# AUDIO.net
KiCad netlist of a schematic drawn in Altium Designer
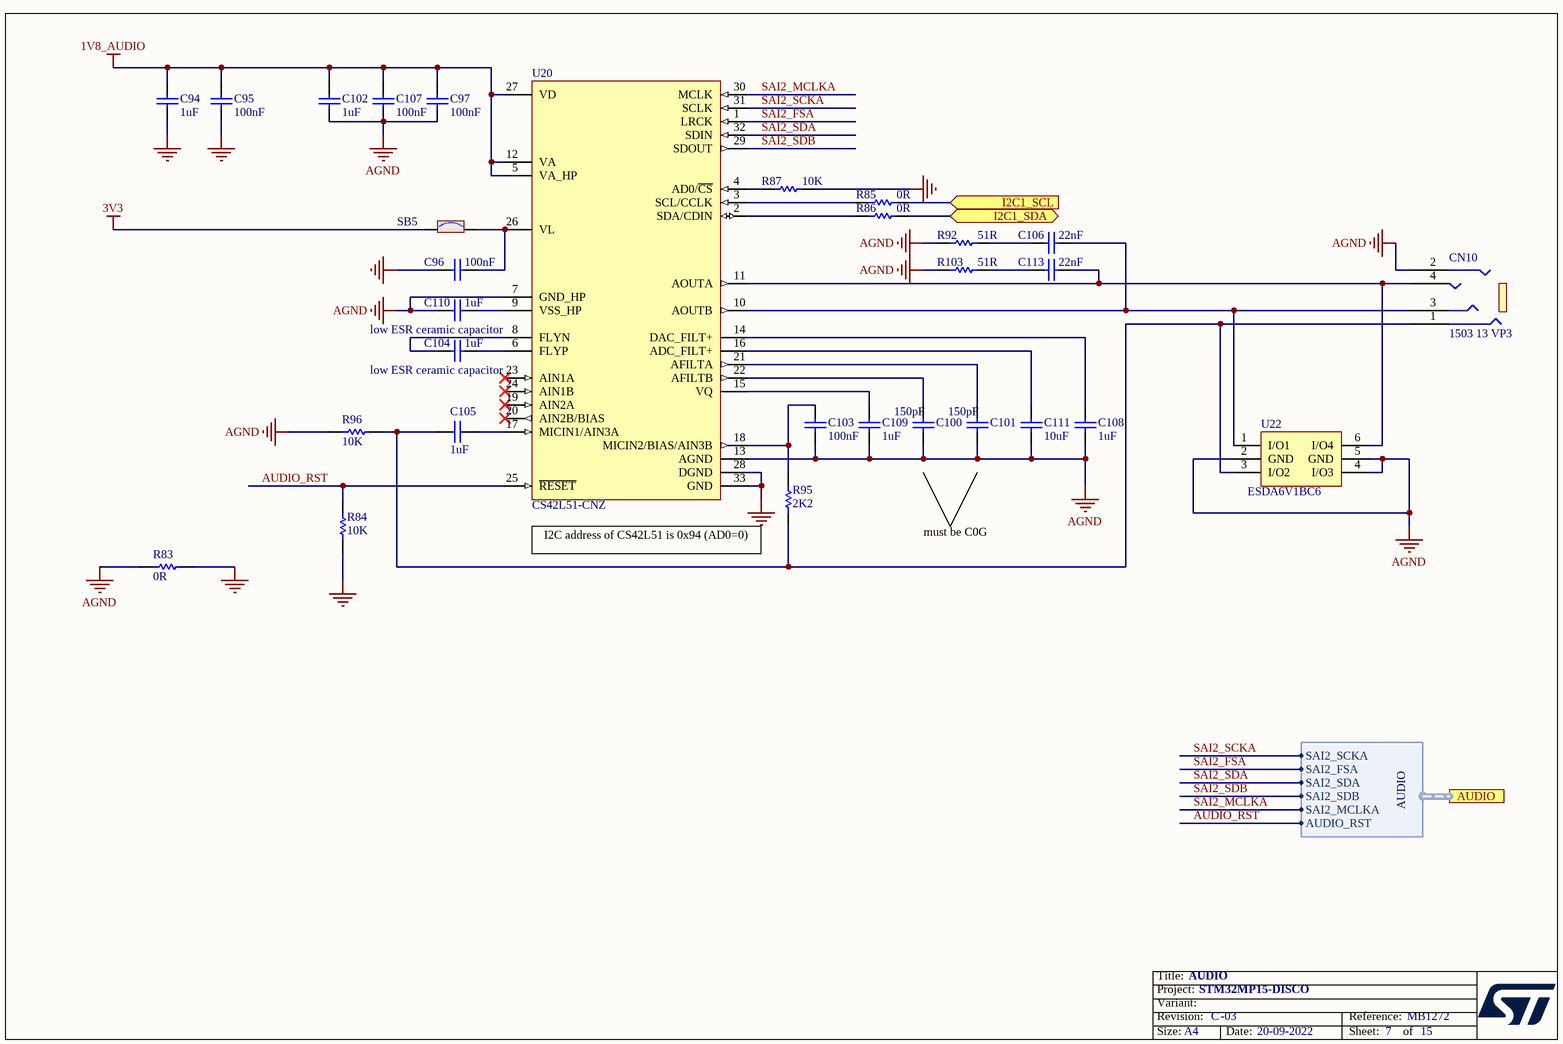
[diagram p0: AUDIO.SchDoc]

(export (version "E")
  (design (tool "Eeschema 10.0.6"))
  (components
    (comp (ref "C94")
      (value "1uF")
      (footprint "C0402")
      (description "Capacitor,1uF,6V3,X5R,10%,0402")
      (fields
        (field (name "INTERNAL_PART_NUMBER") "MCD-00095")
        (field (name "MANUFACTURER_PART_NUMBER") "GRM155R61E105KA12")
        (field (name "PROVIDED_BY") "SUBCO")
      )
      (libsource (lib "MCD_PARTS_database") (part "Capacitor"))
    )
    (comp (ref "C95")
      (value "100nF")
      (footprint "C0402")
      (description "Capacitor,100nF,16V,X7R,10%,0402")
      (fields
        (field (name "INTERNAL_PART_NUMBER") "MCD-00006")
        (field (name "MANUFACTURER_PART_NUMBER") "CC0402KRX7R7BB104")
        (field (name "PROVIDED_BY") "SUBCO")
      )
      (libsource (lib "MCD_PARTS_database") (part "Capacitor"))
    )
    (comp (ref "C96")
      (value "100nF")
      (footprint "C0402")
      (description "Capacitor,100nF,16V,X7R,10%,0402")
      (fields
        (field (name "INTERNAL_PART_NUMBER") "MCD-00006")
        (field (name "MANUFACTURER_PART_NUMBER") "CC0402KRX7R7BB104")
        (field (name "PROVIDED_BY") "SUBCO")
      )
      (libsource (lib "MCD_PARTS_database") (part "Capacitor"))
    )
    (comp (ref "C97")
      (value "100nF")
      (footprint "C0402")
      (description "Capacitor,100nF,16V,X7R,10%,0402")
      (fields
        (field (name "INTERNAL_PART_NUMBER") "MCD-00006")
        (field (name "MANUFACTURER_PART_NUMBER") "CC0402KRX7R7BB104")
        (field (name "PROVIDED_BY") "SUBCO")
      )
      (libsource (lib "MCD_PARTS_database") (part "Capacitor"))
    )
    (comp (ref "C100")
      (value "150pF")
      (footprint "C0603")
      (description "Capacitor,150pF,50V,COG,5%,0603")
      (fields
        (field (name "INTERNAL_PART_NUMBER") "MCD-00304")
        (field (name "MANUFACTURER_PART_NUMBER") "CC0603JRNPO9BN151")
        (field (name "PROVIDED_BY") "SUBCO")
      )
      (libsource (lib "MCD_PARTS_database") (part "Capacitor"))
    )
    (comp (ref "C101")
      (value "150pF")
      (footprint "C0603")
      (description "Capacitor,150pF,50V,COG,5%,0603")
      (fields
        (field (name "INTERNAL_PART_NUMBER") "MCD-00304")
        (field (name "MANUFACTURER_PART_NUMBER") "CC0603JRNPO9BN151")
        (field (name "PROVIDED_BY") "SUBCO")
      )
      (libsource (lib "MCD_PARTS_database") (part "Capacitor"))
    )
    (comp (ref "C102")
      (value "1uF")
      (footprint "C0402")
      (description "Capacitor,1uF,6V3,X5R,10%,0402")
      (fields
        (field (name "INTERNAL_PART_NUMBER") "MCD-00095")
        (field (name "MANUFACTURER_PART_NUMBER") "GRM155R61E105KA12")
        (field (name "PROVIDED_BY") "SUBCO")
      )
      (libsource (lib "MCD_PARTS_database") (part "Capacitor"))
    )
    (comp (ref "C103")
      (value "100nF")
      (footprint "C0402")
      (description "Capacitor,100nF,16V,X7R,10%,0402")
      (fields
        (field (name "INTERNAL_PART_NUMBER") "MCD-00006")
        (field (name "MANUFACTURER_PART_NUMBER") "CC0402KRX7R7BB104")
        (field (name "PROVIDED_BY") "SUBCO")
      )
      (libsource (lib "MCD_PARTS_database") (part "Capacitor"))
    )
    (comp (ref "C104")
      (value "1uF")
      (footprint "C0603")
      (description "Capacitor,1uF,16V,X5R,10%,0603")
      (fields
        (field (name "INTERNAL_PART_NUMBER") "MCD-00010")
        (field (name "MANUFACTURER_PART_NUMBER") "CC0603KRX5R7BB105")
        (field (name "PROVIDED_BY") "SUBCO")
      )
      (libsource (lib "MCD_PARTS_database") (part "Capacitor"))
    )
    (comp (ref "C105")
      (value "1uF")
      (footprint "C0402")
      (description "Capacitor,1uF,6V3,X5R,10%,0402")
      (fields
        (field (name "INTERNAL_PART_NUMBER") "MCD-00095")
        (field (name "MANUFACTURER_PART_NUMBER") "GRM155R61E105KA12")
        (field (name "PROVIDED_BY") "SUBCO")
      )
      (libsource (lib "MCD_PARTS_database") (part "Capacitor"))
    )
    (comp (ref "C106")
      (value "22nF")
      (footprint "C0402")
      (description "Capacitor,22nF,16V,X7R,10%,0402")
      (fields
        (field (name "INTERNAL_PART_NUMBER") "MCD-00202")
        (field (name "MANUFACTURER_PART_NUMBER") "CC0402KRX7R7BB223")
        (field (name "PROVIDED_BY") "SUBCO")
      )
      (libsource (lib "MCD_PARTS_database") (part "Capacitor"))
    )
    (comp (ref "C107")
      (value "100nF")
      (footprint "C0402")
      (description "Capacitor,100nF,16V,X7R,10%,0402")
      (fields
        (field (name "INTERNAL_PART_NUMBER") "MCD-00006")
        (field (name "MANUFACTURER_PART_NUMBER") "CC0402KRX7R7BB104")
        (field (name "PROVIDED_BY") "SUBCO")
      )
      (libsource (lib "MCD_PARTS_database") (part "Capacitor"))
    )
    (comp (ref "C108")
      (value "1uF")
      (footprint "C0402")
      (description "Capacitor,1uF,6V3,X5R,10%,0402")
      (fields
        (field (name "INTERNAL_PART_NUMBER") "MCD-00095")
        (field (name "MANUFACTURER_PART_NUMBER") "GRM155R61E105KA12")
        (field (name "PROVIDED_BY") "SUBCO")
      )
      (libsource (lib "MCD_PARTS_database") (part "Capacitor"))
    )
    (comp (ref "C109")
      (value "1uF")
      (footprint "C0402")
      (description "Capacitor,1uF,6V3,X5R,10%,0402")
      (fields
        (field (name "INTERNAL_PART_NUMBER") "MCD-00095")
        (field (name "MANUFACTURER_PART_NUMBER") "GRM155R61E105KA12")
        (field (name "PROVIDED_BY") "SUBCO")
      )
      (libsource (lib "MCD_PARTS_database") (part "Capacitor"))
    )
    (comp (ref "C110")
      (value "1uF")
      (footprint "C0603")
      (description "Capacitor,1uF,16V,X5R,10%,0603")
      (fields
        (field (name "INTERNAL_PART_NUMBER") "MCD-00010")
        (field (name "MANUFACTURER_PART_NUMBER") "CC0603KRX5R7BB105")
        (field (name "PROVIDED_BY") "SUBCO")
      )
      (libsource (lib "MCD_PARTS_database") (part "Capacitor"))
    )
    (comp (ref "C111")
      (value "10uF")
      (footprint "C0603")
      (description "Capacitor,10uF,6V3,X5R,10%,0603")
      (fields
        (field (name "INTERNAL_PART_NUMBER") "MCD-00098")
        (field (name "MANUFACTURER_PART_NUMBER") "CC0603KRX5R5BB106")
        (field (name "PROVIDED_BY") "SUBCO")
      )
      (libsource (lib "MCD_PARTS_database") (part "Capacitor"))
    )
    (comp (ref "C113")
      (value "22nF")
      (footprint "C0402")
      (description "Capacitor,22nF,16V,X7R,10%,0402")
      (fields
        (field (name "INTERNAL_PART_NUMBER") "MCD-00202")
        (field (name "MANUFACTURER_PART_NUMBER") "CC0402KRX7R7BB223")
        (field (name "PROVIDED_BY") "SUBCO")
      )
      (libsource (lib "MCD_PARTS_database") (part "Capacitor"))
    )
    (comp (ref "CN10")
      (value "1503 13 VP3")
      (footprint "CON_JACK-3P5-SMT_LUMBERG_1503-13-VP3")
      (description "Connector Jack socket Stereo 3.5mm, 4 pins, RA, SMT, Black")
      (fields
        (field (name "INTERNAL_PART_NUMBER") "MCD-00270")
        (field (name "MANUFACTURER") "LUMBERG")
        (field (name "PROVIDED_BY") "SUBCO")
      )
      (libsource (lib "MCD_PARTS_database") (part "Jack_1503 13 VP3"))
    )
    (comp (ref "R83")
      (value "0R")
      (footprint "R0603")
      (description "Resistor,0R,0603,5%,1/10W")
      (fields
        (field (name "INTERNAL_PART_NUMBER") "MCD-00056")
        (field (name "MANUFACTURER_PART_NUMBER") "RC0603JR-070RL")
        (field (name "PROVIDED_BY") "SUBCO")
      )
      (libsource (lib "MCD_PARTS_database") (part "Resistor"))
    )
    (comp (ref "R84")
      (value "10K")
      (footprint "R0402")
      (description "Resistor,10K,0402,1%,1/16W")
      (fields
        (field (name "INTERNAL_PART_NUMBER") "MCD-00053")
        (field (name "MANUFACTURER_PART_NUMBER") "RC0402FR-0710KL")
        (field (name "PROVIDED_BY") "SUBCO")
      )
      (libsource (lib "MCD_PARTS_database") (part "Resistor"))
    )
    (comp (ref "R85")
      (value "0R")
      (footprint "R0402")
      (description "Resistor,0R,0402,5%,1/16W")
      (fields
        (field (name "INTERNAL_PART_NUMBER") "MCD-00052")
        (field (name "MANUFACTURER_PART_NUMBER") "RC0402JR-070RL")
        (field (name "PROVIDED_BY") "SUBCO")
      )
      (libsource (lib "MCD_PARTS_database") (part "Resistor"))
    )
    (comp (ref "R86")
      (value "0R")
      (footprint "R0402")
      (description "Resistor,0R,0402,5%,1/16W")
      (fields
        (field (name "INTERNAL_PART_NUMBER") "MCD-00052")
        (field (name "MANUFACTURER_PART_NUMBER") "RC0402JR-070RL")
        (field (name "PROVIDED_BY") "SUBCO")
      )
      (libsource (lib "MCD_PARTS_database") (part "Resistor"))
    )
    (comp (ref "R87")
      (value "10K")
      (footprint "R0402")
      (description "Resistor,10K,0402,1%,1/16W")
      (fields
        (field (name "INTERNAL_PART_NUMBER") "MCD-00053")
        (field (name "MANUFACTURER_PART_NUMBER") "RC0402FR-0710KL")
        (field (name "PROVIDED_BY") "SUBCO")
      )
      (libsource (lib "MCD_PARTS_database") (part "Resistor"))
    )
    (comp (ref "R92")
      (value "51R")
      (footprint "R0402")
      (description "Resistor,51R,0402,1%,1/16W")
      (fields
        (field (name "INTERNAL_PART_NUMBER") "MCD-00485")
        (field (name "MANUFACTURER_PART_NUMBER") "RC0402FR-0751RL")
        (field (name "PROVIDED_BY") "SUBCO")
      )
      (libsource (lib "MCD_PARTS_database") (part "Resistor"))
    )
    (comp (ref "R95")
      (value "2K2")
      (footprint "R0402")
      (description "Resistor,2K2,0402,1%,1/16W")
      (fields
        (field (name "INTERNAL_PART_NUMBER") "MCD-00057")
        (field (name "MANUFACTURER_PART_NUMBER") "RC0402FR-072K2L")
        (field (name "PROVIDED_BY") "SUBCO")
      )
      (libsource (lib "MCD_PARTS_database") (part "Resistor"))
    )
    (comp (ref "R96")
      (value "10K")
      (footprint "R0402")
      (description "Resistor,10K,0402,1%,1/16W")
      (fields
        (field (name "INTERNAL_PART_NUMBER") "MCD-00053")
        (field (name "MANUFACTURER_PART_NUMBER") "RC0402FR-0710KL")
        (field (name "PROVIDED_BY") "SUBCO")
      )
      (libsource (lib "MCD_PARTS_database") (part "Resistor"))
    )
    (comp (ref "R103")
      (value "51R")
      (footprint "R0402")
      (description "Resistor,51R,0402,1%,1/16W")
      (fields
        (field (name "INTERNAL_PART_NUMBER") "MCD-00485")
        (field (name "MANUFACTURER_PART_NUMBER") "RC0402FR-0751RL")
        (field (name "PROVIDED_BY") "SUBCO")
      )
      (libsource (lib "MCD_PARTS_database") (part "Resistor"))
    )
    (comp (ref "SB5")
      (value "~")
      (footprint "SOLDER-BRIDGE_R0603-0R")
      (description "Solder Bridge ON")
      (fields
        (field (name "INTERNAL_PART_NUMBER") "MCD-00071")
        (field (name "MANUFACTURER") "YAGEO")
        (field (name "PROVIDED_BY") "SUBCO")
      )
      (libsource (lib "MCD_PARTS_database") (part "SB_ON"))
    )
    (comp (ref "U20")
      (value "CS42L51-CNZ")
      (footprint "ICC_QFN32-EPAD_5X5_P050")
      (description "Low-Power, Stereo Codec with Headphone Amp")
      (fields
        (field (name "INTERNAL_PART_NUMBER") "MCD-00265")
        (field (name "MANUFACTURER") "CIRRUS LOGIC")
        (field (name "PROVIDED_BY") "SUBCO")
      )
      (libsource (lib "MCD_PARTS_database") (part "CS42L51-CNZ"))
    )
    (comp (ref "U22")
      (value "ESDA6V1BC6")
      (footprint "ESD_SOT23-6L")
      (description "Quad Bidir ESD protection")
      (fields
        (field (name "INTERNAL_PART_NUMBER") "MCD-00247")
        (field (name "MANUFACTURER") "STMICROELECTRONICS")
        (field (name "PROVIDED_BY") "SUBCO with ST control")
      )
      (libsource (lib "MCD_PARTS_database") (part "ESDA6V1BC6"))
    )
  )
  (nets
    (net (code "2") (name "/AUDIO_RST") (class "Default")
      (node (ref "R84") (pin "2") (pinfunction "2_2") (pintype "passive"))
      (node (ref "U20") (pin "25") (pinfunction "~{RESET}_25") (pintype "input"))
    )
    (net (code "3") (name "/I2C1_SCL") (class "Default")
      (node (ref "R85") (pin "2") (pinfunction "2_2") (pintype "passive"))
    )
    (net (code "4") (name "/I2C1_SDA") (class "Default")
      (node (ref "R86") (pin "2") (pinfunction "2_2") (pintype "passive"))
    )
    (net (code "5") (name "/SAI2_FSA") (class "Default")
      (node (ref "U20") (pin "1") (pinfunction "LRCK_1") (pintype "input"))
    )
    (net (code "6") (name "/SAI2_MCLKA") (class "Default")
      (node (ref "U20") (pin "30") (pinfunction "MCLK_30") (pintype "input"))
    )
    (net (code "7") (name "/SAI2_SCKA") (class "Default")
      (node (ref "U20") (pin "31") (pinfunction "SCLK_31") (pintype "input"))
    )
    (net (code "8") (name "/SAI2_SDA") (class "Default")
      (node (ref "U20") (pin "32") (pinfunction "SDIN_32") (pintype "input"))
    )
    (net (code "9") (name "/SAI2_SDB") (class "Default")
      (node (ref "U20") (pin "29") (pinfunction "SDOUT_29") (pintype "output"))
    )
    (net (code "11") (name "1V8_AUDIO") (class "Default")
      (node (ref "C102") (pin "2") (pinfunction "2_2") (pintype "passive"))
      (node (ref "C107") (pin "2") (pinfunction "2_2") (pintype "passive"))
      (node (ref "C94") (pin "2") (pinfunction "2_2") (pintype "passive"))
      (node (ref "C95") (pin "2") (pinfunction "2_2") (pintype "passive"))
      (node (ref "C97") (pin "2") (pinfunction "2_2") (pintype "passive"))
      (node (ref "U20") (pin "12") (pinfunction "VA_12") (pintype "power_in"))
      (node (ref "U20") (pin "27") (pinfunction "VD_27") (pintype "power_in"))
      (node (ref "U20") (pin "5") (pinfunction "VA_HP_5") (pintype "power_in"))
    )
    (net (code "12") (name "3V3") (class "Default")
      (node (ref "SB5") (pin "1") (pinfunction "1_1") (pintype "passive"))
    )
    (net (code "13") (name "AGND") (class "Default")
      (node (ref "C100") (pin "1") (pinfunction "1_1") (pintype "passive"))
      (node (ref "C101") (pin "1") (pinfunction "1_1") (pintype "passive"))
      (node (ref "C102") (pin "1") (pinfunction "1_1") (pintype "passive"))
      (node (ref "C103") (pin "1") (pinfunction "1_1") (pintype "passive"))
      (node (ref "C107") (pin "1") (pinfunction "1_1") (pintype "passive"))
      (node (ref "C108") (pin "1") (pinfunction "1_1") (pintype "passive"))
      (node (ref "C109") (pin "1") (pinfunction "1_1") (pintype "passive"))
      (node (ref "C110") (pin "1") (pinfunction "1_1") (pintype "passive"))
      (node (ref "C111") (pin "1") (pinfunction "1_1") (pintype "passive"))
      (node (ref "C97") (pin "1") (pinfunction "1_1") (pintype "passive"))
      (node (ref "CN10") (pin "2") (pintype "passive"))
      (node (ref "R103") (pin "1") (pinfunction "1_1") (pintype "passive"))
      (node (ref "R83") (pin "1") (pinfunction "1_1") (pintype "passive"))
      (node (ref "R92") (pin "1") (pinfunction "1_1") (pintype "passive"))
      (node (ref "R96") (pin "1") (pinfunction "1_1") (pintype "passive"))
      (node (ref "U20") (pin "13") (pinfunction "AGND_13") (pintype "power_in"))
      (node (ref "U20") (pin "7") (pinfunction "GND_HP_7") (pintype "power_in"))
      (node (ref "U22") (pin "2") (pinfunction "GND_2") (pintype "passive"))
      (node (ref "U22") (pin "4") (pinfunction "I/O3_4") (pintype "passive"))
      (node (ref "U22") (pin "5") (pinfunction "GND_5") (pintype "passive"))
    )
    (net (code "14") (name "GND") (class "Default")
      (node (ref "C94") (pin "1") (pinfunction "1_1") (pintype "passive"))
      (node (ref "C95") (pin "1") (pinfunction "1_1") (pintype "passive"))
      (node (ref "C96") (pin "2") (pinfunction "2_2") (pintype "passive"))
      (node (ref "R83") (pin "2") (pinfunction "2_2") (pintype "passive"))
      (node (ref "R84") (pin "1") (pinfunction "1_1") (pintype "passive"))
      (node (ref "R87") (pin "2") (pinfunction "2_2") (pintype "passive"))
      (node (ref "U20") (pin "28") (pinfunction "DGND_28") (pintype "power_in"))
      (node (ref "U20") (pin "33") (pinfunction "GND_33") (pintype "power_in"))
    )
    (net (code "15") (name "Net-(C106-Pad1)") (class "Default")
      (node (ref "C106") (pin "1") (pinfunction "1_1") (pintype "passive"))
      (node (ref "R92") (pin "2") (pinfunction "2_2") (pintype "passive"))
    )
    (net (code "16") (name "Net-(C113-Pad1)") (class "Default")
      (node (ref "C113") (pin "1") (pinfunction "1_1") (pintype "passive"))
      (node (ref "R103") (pin "2") (pinfunction "2_2") (pintype "passive"))
    )
    (net (code "17") (name "Net-(U20-AD0{slash}~{CS})") (class "Default")
      (node (ref "R87") (pin "1") (pinfunction "1_1") (pintype "passive"))
      (node (ref "U20") (pin "4") (pinfunction "AD0/~{CS}_4") (pintype "input"))
    )
    (net (code "18") (name "Net-(U20-ADC_FILT+)") (class "Default")
      (node (ref "C111") (pin "2") (pinfunction "2_2") (pintype "passive"))
      (node (ref "U20") (pin "16") (pinfunction "ADC_FILT+_16") (pintype "power_in"))
    )
    (net (code "19") (name "Net-(U20-AFILTA)") (class "Default")
      (node (ref "C101") (pin "2") (pinfunction "2_2") (pintype "passive"))
      (node (ref "U20") (pin "21") (pinfunction "AFILTA_21") (pintype "output"))
    )
    (net (code "20") (name "Net-(U20-AFILTB)") (class "Default")
      (node (ref "C100") (pin "2") (pinfunction "2_2") (pintype "passive"))
      (node (ref "U20") (pin "22") (pinfunction "AFILTB_22") (pintype "output"))
    )
    (net (code "21") (name "Net-(U20-AOUTA)") (class "Default")
      (node (ref "C113") (pin "2") (pinfunction "2_2") (pintype "passive"))
      (node (ref "CN10") (pin "4") (pintype "passive"))
      (node (ref "U20") (pin "11") (pinfunction "AOUTA_11") (pintype "output"))
      (node (ref "U22") (pin "6") (pinfunction "I/O4_6") (pintype "passive"))
    )
    (net (code "22") (name "Net-(U20-AOUTB)") (class "Default")
      (node (ref "C106") (pin "2") (pinfunction "2_2") (pintype "passive"))
      (node (ref "CN10") (pin "3") (pintype "passive"))
      (node (ref "U20") (pin "10") (pinfunction "AOUTB_10") (pintype "output"))
      (node (ref "U22") (pin "1") (pinfunction "I/O1_1") (pintype "passive"))
    )
    (net (code "23") (name "Net-(U20-DAC_FILT+)") (class "Default")
      (node (ref "C108") (pin "2") (pinfunction "2_2") (pintype "passive"))
      (node (ref "U20") (pin "14") (pinfunction "DAC_FILT+_14") (pintype "power_in"))
    )
    (net (code "24") (name "Net-(U20-FLYN)") (class "Default")
      (node (ref "C104") (pin "1") (pinfunction "1_1") (pintype "passive"))
      (node (ref "U20") (pin "8") (pinfunction "FLYN_8") (pintype "passive"))
    )
    (net (code "25") (name "Net-(U20-FLYP)") (class "Default")
      (node (ref "C104") (pin "2") (pinfunction "2_2") (pintype "passive"))
      (node (ref "U20") (pin "6") (pinfunction "FLYP_6") (pintype "passive"))
    )
    (net (code "26") (name "Net-(U20-MICIN1{slash}AIN3A)") (class "Default")
      (node (ref "C105") (pin "2") (pinfunction "2_2") (pintype "passive"))
      (node (ref "U20") (pin "17") (pinfunction "MICIN1/AIN3A_17") (pintype "input"))
    )
    (net (code "27") (name "Net-(U20-MICIN2{slash}BIAS{slash}AIN3B)") (class "Default")
      (node (ref "C103") (pin "2") (pinfunction "2_2") (pintype "passive"))
      (node (ref "R95") (pin "2") (pinfunction "2_2") (pintype "passive"))
      (node (ref "U20") (pin "18") (pinfunction "MICIN2/BIAS/AIN3B_18") (pintype "output"))
    )
    (net (code "28") (name "Net-(U20-SCL{slash}CCLK)") (class "Default")
      (node (ref "R85") (pin "1") (pinfunction "1_1") (pintype "passive"))
      (node (ref "U20") (pin "3") (pinfunction "SCL/CCLK_3") (pintype "input"))
    )
    (net (code "29") (name "Net-(U20-SDA{slash}CDIN)") (class "Default")
      (node (ref "R86") (pin "1") (pinfunction "1_1") (pintype "passive"))
      (node (ref "U20") (pin "2") (pinfunction "SDA/CDIN_2") (pintype "bidirectional"))
    )
    (net (code "30") (name "Net-(U20-VL)") (class "Default")
      (node (ref "C96") (pin "1") (pinfunction "1_1") (pintype "passive"))
      (node (ref "SB5") (pin "2") (pinfunction "2_2") (pintype "passive"))
      (node (ref "U20") (pin "26") (pinfunction "VL_26") (pintype "power_in"))
    )
    (net (code "31") (name "Net-(U20-VQ)") (class "Default")
      (node (ref "C109") (pin "2") (pinfunction "2_2") (pintype "passive"))
      (node (ref "U20") (pin "15") (pinfunction "VQ_15") (pintype "power_in"))
    )
    (net (code "32") (name "Net-(U20-VSS_HP)") (class "Default")
      (node (ref "C110") (pin "2") (pinfunction "2_2") (pintype "passive"))
      (node (ref "U20") (pin "9") (pinfunction "VSS_HP_9") (pintype "power_in"))
    )
    (net (code "33") (name "Net-(U22-I{slash}O2)") (class "Default")
      (node (ref "C105") (pin "1") (pinfunction "1_1") (pintype "passive"))
      (node (ref "CN10") (pin "1") (pintype "passive"))
      (node (ref "R95") (pin "1") (pinfunction "1_1") (pintype "passive"))
      (node (ref "R96") (pin "2") (pinfunction "2_2") (pintype "passive"))
      (node (ref "U22") (pin "3") (pinfunction "I/O2_3") (pintype "passive"))
    )
    (net (code "34") (name "unconnected-(U20-AIN1A-Pad23)") (class "Default")
      (node (ref "U20") (pin "23") (pinfunction "AIN1A_23") (pintype "input+no_connect"))
    )
    (net (code "35") (name "unconnected-(U20-AIN1B-Pad24)") (class "Default")
      (node (ref "U20") (pin "24") (pinfunction "AIN1B_24") (pintype "input+no_connect"))
    )
    (net (code "36") (name "unconnected-(U20-AIN2A-Pad19)") (class "Default")
      (node (ref "U20") (pin "19") (pinfunction "AIN2A_19") (pintype "input+no_connect"))
    )
    (net (code "37") (name "unconnected-(U20-AIN2B{slash}BIAS-Pad20)") (class "Default")
      (node (ref "U20") (pin "20") (pinfunction "AIN2B/BIAS_20") (pintype "output+no_connect"))
    )
  )
)
